# Filamint_Schematic_V4_1.net
KiCad netlist of a schematic drawn in EAGLE
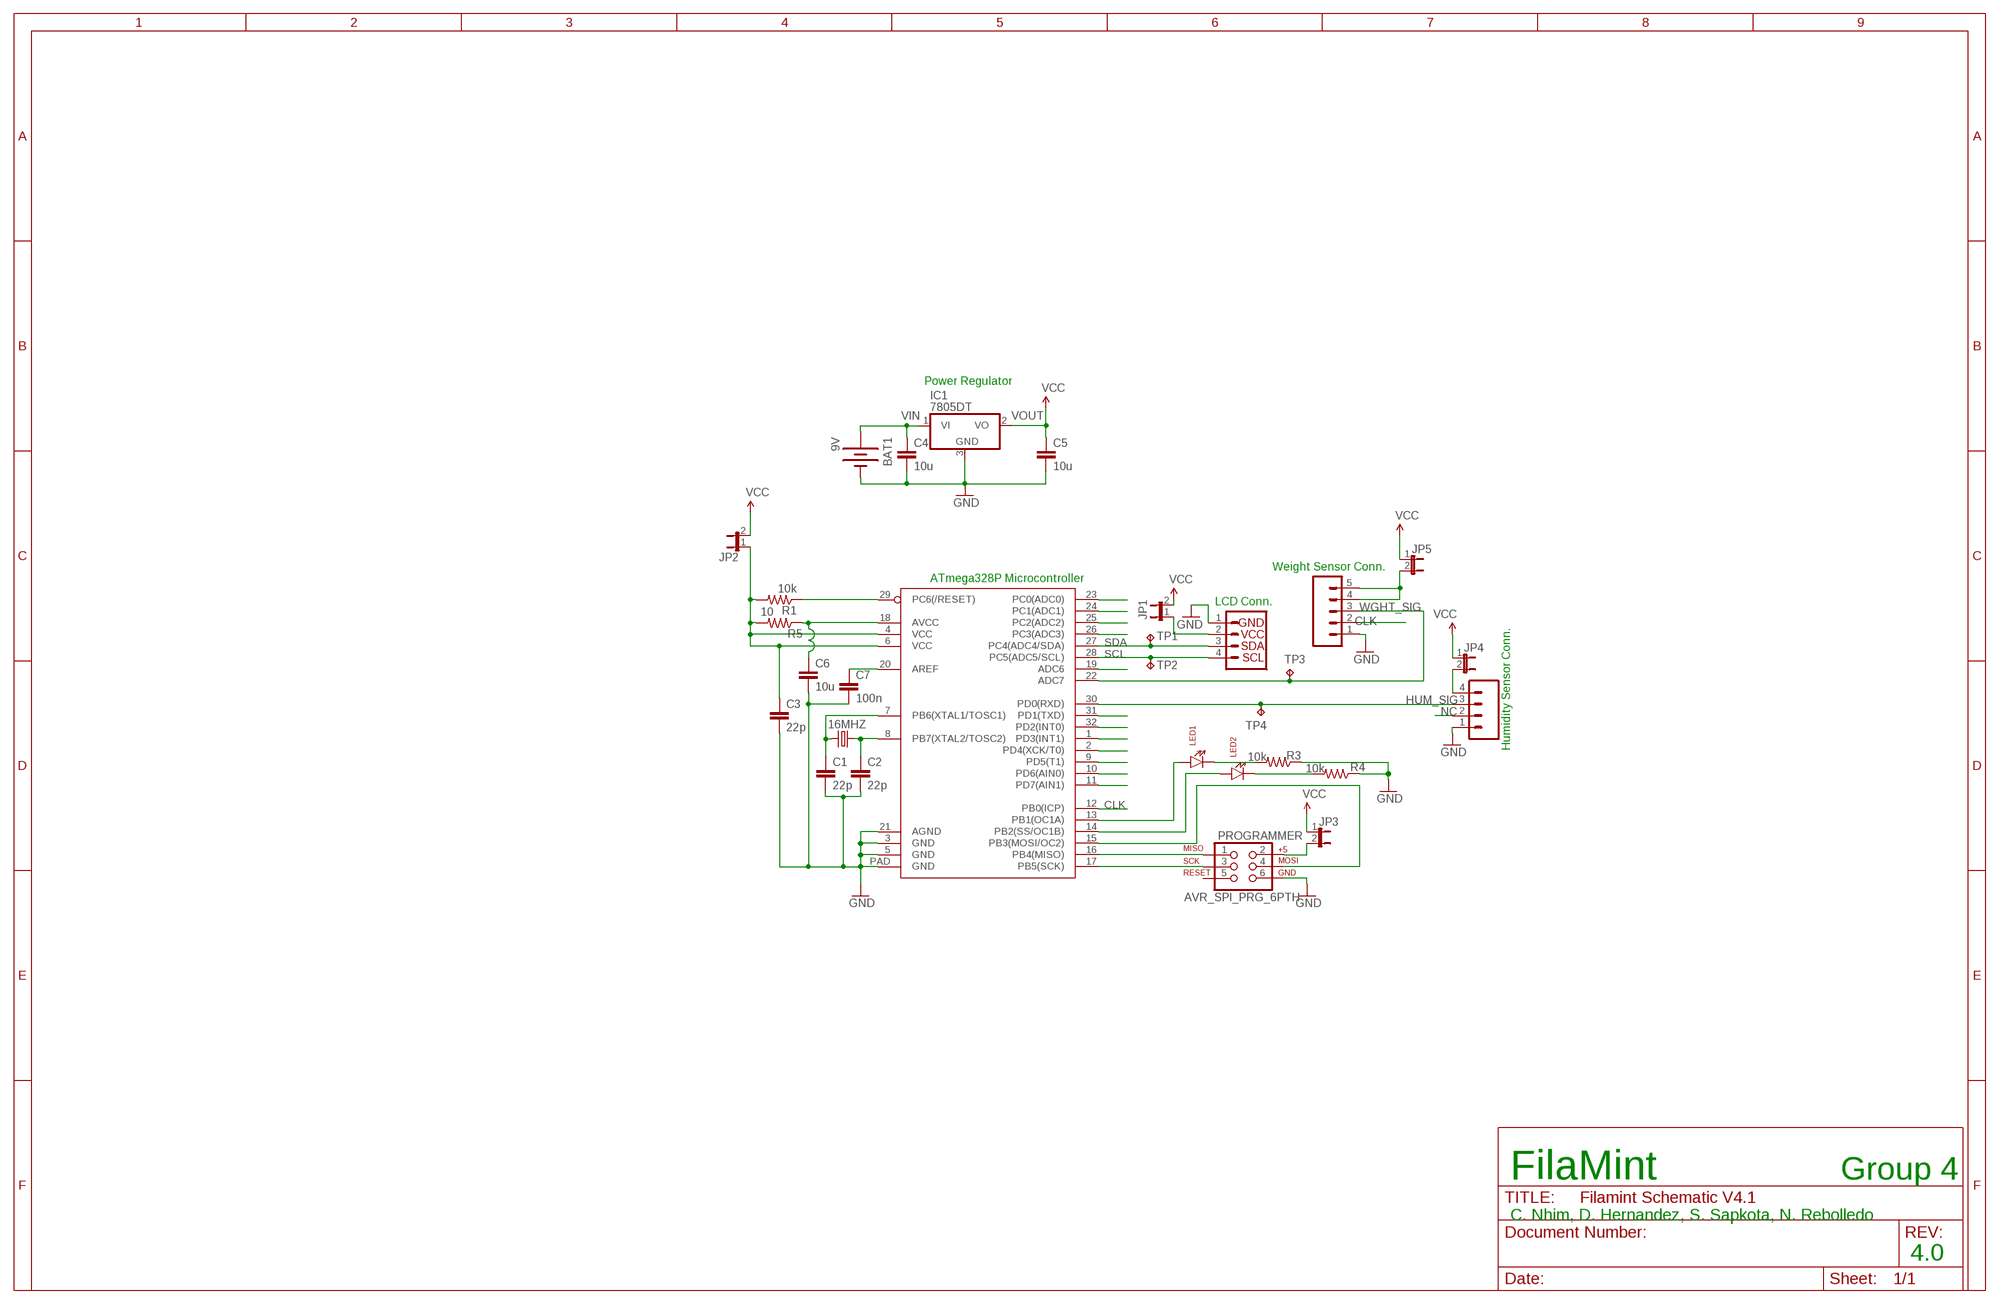
[diagram p0: schematic, sheet 1]

(export (version "E")
  (design (tool "Eeschema 10.0.6"))
  (components
    (comp (ref "16MHZ")
      (value "CSM-7X-DU")
      (footprint "eagle-import:CSM-7X-DU")
      (libsource (lib "eagle-import") (part "CSM-7X-DU"))
    )
    (comp (ref "BAT1")
      (value "9V")
      (footprint "eagle-import:BATTCON_9V")
      (libsource (lib "eagle-import") (part "BATTERY9V"))
    )
    (comp (ref "C1")
      (value "22p")
      (footprint "eagle-import:C025-024X044")
      (libsource (lib "eagle-import") (part "C-EU025-024X044"))
    )
    (comp (ref "C2")
      (value "22p")
      (footprint "eagle-import:C025-024X044")
      (libsource (lib "eagle-import") (part "C-EU025-024X044"))
    )
    (comp (ref "C3")
      (value "22p")
      (footprint "eagle-import:C025-024X044")
      (libsource (lib "eagle-import") (part "C-EU025-024X044"))
    )
    (comp (ref "C4")
      (value "10u")
      (footprint "eagle-import:C025-024X044")
      (libsource (lib "eagle-import") (part "C-EU025-024X044"))
    )
    (comp (ref "C5")
      (value "10u")
      (footprint "eagle-import:C025-024X044")
      (libsource (lib "eagle-import") (part "C-EU025-024X044"))
    )
    (comp (ref "C6")
      (value "10u")
      (footprint "eagle-import:C025-024X044")
      (libsource (lib "eagle-import") (part "C-EU025-024X044"))
    )
    (comp (ref "C7")
      (value "100n")
      (footprint "eagle-import:C025-024X044")
      (libsource (lib "eagle-import") (part "C-EU025-024X044"))
    )
    (comp (ref "DHT22")
      (value "M04SMD2")
      (footprint "eagle-import:1X04-1MM-RA")
      (libsource (lib "eagle-import") (part "M04SMD2"))
    )
    (comp (ref "HX711")
      (value "M05SMD")
      (footprint "eagle-import:1X05-1MM")
      (libsource (lib "eagle-import") (part "M05SMD"))
    )
    (comp (ref "IC1")
      (value "7805DT")
      (footprint "eagle-import:TO252")
      (libsource (lib "eagle-import") (part "78DT05"))
    )
    (comp (ref "JP1")
      (value "JP1E")
      (footprint "eagle-import:JP1")
      (libsource (lib "eagle-import") (part "JP1E"))
    )
    (comp (ref "JP2")
      (value "JP1E")
      (footprint "eagle-import:JP1")
      (libsource (lib "eagle-import") (part "JP1E"))
    )
    (comp (ref "JP3")
      (value "JP1E")
      (footprint "eagle-import:JP1")
      (libsource (lib "eagle-import") (part "JP1E"))
    )
    (comp (ref "JP4")
      (value "JP1E")
      (footprint "eagle-import:JP1")
      (libsource (lib "eagle-import") (part "JP1E"))
    )
    (comp (ref "JP5")
      (value "JP1E")
      (footprint "eagle-import:JP1")
      (libsource (lib "eagle-import") (part "JP1E"))
    )
    (comp (ref "LCD")
      (value "I2C_STANDARD")
      (footprint "eagle-import:1X04")
      (libsource (lib "eagle-import") (part "I2C_STANDARD"))
    )
    (comp (ref "LED1")
      (value "LTE-302")
      (footprint "eagle-import:LTE-302")
      (libsource (lib "eagle-import") (part "LTE-302"))
    )
    (comp (ref "LED2")
      (value "LTE-302")
      (footprint "eagle-import:LTE-302")
      (libsource (lib "eagle-import") (part "LTE-302"))
    )
    (comp (ref "MICROCONTROLLER")
      (value "ATMEGA328P_MLFMLF32")
      (footprint "eagle-import:MLF32-PAD")
      (libsource (lib "eagle-import") (part "ATMEGA328P_MLFMLF32"))
    )
    (comp (ref "PROGRAMMER")
      (value "AVR_SPI_PRG_6PTH")
      (footprint "eagle-import:2X3")
      (libsource (lib "eagle-import") (part "AVR_SPI_PRG_6PTH"))
    )
    (comp (ref "R1")
      (value "10k")
      (footprint "eagle-import:0204_5")
      (libsource (lib "eagle-import") (part "R-US_0204/5"))
    )
    (comp (ref "R3")
      (value "10k")
      (footprint "eagle-import:0204_5")
      (libsource (lib "eagle-import") (part "R-US_0204/5"))
    )
    (comp (ref "R4")
      (value "10k")
      (footprint "eagle-import:0204_5")
      (libsource (lib "eagle-import") (part "R-US_0204/5"))
    )
    (comp (ref "R5")
      (value "10")
      (footprint "eagle-import:0204_5")
      (libsource (lib "eagle-import") (part "R-US_0204/5"))
    )
    (comp (ref "TP1")
      (value "TPB1,27")
      (footprint "eagle-import:B1,27")
      (libsource (lib "eagle-import") (part "TPB1,27"))
    )
    (comp (ref "TP2")
      (value "TPB1,27")
      (footprint "eagle-import:B1,27")
      (libsource (lib "eagle-import") (part "TPB1,27"))
    )
    (comp (ref "TP3")
      (value "TPB1,27")
      (footprint "eagle-import:B1,27")
      (libsource (lib "eagle-import") (part "TPB1,27"))
    )
    (comp (ref "TP4")
      (value "TPB1,27")
      (footprint "eagle-import:B1,27")
      (libsource (lib "eagle-import") (part "TPB1,27"))
    )
  )
  (nets
    (net (code "1") (name "/CLK") (class "Default")
      (node (ref "HX711") (pin "2") (pinfunction "2_2") (pintype "passive"))
      (node (ref "MICROCONTROLLER") (pin "12") (pinfunction "PB0(ICP)_12") (pintype "bidirectional"))
    )
    (net (code "2") (name "/HUM_SIG") (class "Default")
      (node (ref "DHT22") (pin "3") (pinfunction "3_3") (pintype "passive"))
      (node (ref "MICROCONTROLLER") (pin "30") (pinfunction "PD0(RXD)_30") (pintype "bidirectional"))
      (node (ref "TP4") (pin "TP") (pinfunction "TP_TP") (pintype "input"))
    )
    (net (code "3") (name "/NC") (class "Default")
      (node (ref "DHT22") (pin "2") (pinfunction "2_2") (pintype "passive"))
    )
    (net (code "4") (name "/SCL") (class "Default")
      (node (ref "LCD") (pin "4") (pinfunction "4_4") (pintype "passive"))
      (node (ref "MICROCONTROLLER") (pin "28") (pinfunction "PC5(ADC5/SCL)_28") (pintype "bidirectional"))
      (node (ref "TP2") (pin "TP") (pinfunction "TP_TP") (pintype "input"))
    )
    (net (code "5") (name "/SDA") (class "Default")
      (node (ref "LCD") (pin "3") (pinfunction "3_3") (pintype "passive"))
      (node (ref "MICROCONTROLLER") (pin "27") (pinfunction "PC4(ADC4/SDA)_27") (pintype "bidirectional"))
      (node (ref "TP1") (pin "TP") (pinfunction "TP_TP") (pintype "input"))
    )
    (net (code "6") (name "/VIN") (class "Default")
      (node (ref "BAT1") (pin "+") (pinfunction "+_+") (pintype "power_in"))
      (node (ref "C4") (pin "1") (pinfunction "1_1") (pintype "passive"))
      (node (ref "IC1") (pin "1") (pinfunction "VI_1") (pintype "input"))
    )
    (net (code "7") (name "/WGHT_SIG") (class "Default")
      (node (ref "HX711") (pin "3") (pinfunction "3_3") (pintype "passive"))
      (node (ref "MICROCONTROLLER") (pin "22") (pinfunction "ADC7_22") (pintype "bidirectional"))
      (node (ref "TP3") (pin "TP") (pinfunction "TP_TP") (pintype "input"))
    )
    (net (code "8") (name "GND") (class "Default")
      (node (ref "BAT1") (pin "-") (pinfunction "-_-") (pintype "power_in"))
      (node (ref "C1") (pin "2") (pinfunction "2_2") (pintype "passive"))
      (node (ref "C2") (pin "2") (pinfunction "2_2") (pintype "passive"))
      (node (ref "C3") (pin "2") (pinfunction "2_2") (pintype "passive"))
      (node (ref "C4") (pin "2") (pinfunction "2_2") (pintype "passive"))
      (node (ref "C5") (pin "2") (pinfunction "2_2") (pintype "passive"))
      (node (ref "C6") (pin "2") (pinfunction "2_2") (pintype "passive"))
      (node (ref "C7") (pin "2") (pinfunction "2_2") (pintype "passive"))
      (node (ref "DHT22") (pin "1") (pinfunction "1_1") (pintype "passive"))
      (node (ref "HX711") (pin "1") (pinfunction "1_1") (pintype "passive"))
      (node (ref "IC1") (pin "3") (pinfunction "GND_3") (pintype "passive"))
      (node (ref "LCD") (pin "1") (pinfunction "1_1") (pintype "passive"))
      (node (ref "MICROCONTROLLER") (pin "21") (pinfunction "AGND_21") (pintype "bidirectional"))
      (node (ref "MICROCONTROLLER") (pin "3") (pinfunction "GND_3") (pintype "bidirectional"))
      (node (ref "MICROCONTROLLER") (pin "5") (pinfunction "GND_5") (pintype "bidirectional"))
      (node (ref "MICROCONTROLLER") (pin "PAD") (pinfunction "GND_PAD") (pintype "bidirectional"))
      (node (ref "PROGRAMMER") (pin "6") (pinfunction "6_6") (pintype "passive"))
      (node (ref "R3") (pin "1") (pinfunction "1_1") (pintype "passive"))
      (node (ref "R4") (pin "1") (pinfunction "1_1") (pintype "passive"))
    )
    (net (code "9") (name "Net-(C3-Pad1)") (class "Default")
      (node (ref "C3") (pin "1") (pinfunction "1_1") (pintype "passive"))
      (node (ref "JP2") (pin "1") (pinfunction "1_1") (pintype "passive"))
      (node (ref "MICROCONTROLLER") (pin "4") (pinfunction "VCC_4") (pintype "bidirectional"))
      (node (ref "MICROCONTROLLER") (pin "6") (pinfunction "VCC_6") (pintype "bidirectional"))
      (node (ref "R1") (pin "2") (pinfunction "2_2") (pintype "passive"))
      (node (ref "R5") (pin "2") (pinfunction "2_2") (pintype "passive"))
    )
    (net (code "10") (name "Net-(DHT22-Pad4)") (class "Default")
      (node (ref "DHT22") (pin "4") (pinfunction "4_4") (pintype "passive"))
      (node (ref "JP4") (pin "2") (pinfunction "2_2") (pintype "passive"))
    )
    (net (code "11") (name "Net-(HX711-Pad4)") (class "Default")
      (node (ref "HX711") (pin "4") (pinfunction "4_4") (pintype "passive"))
      (node (ref "HX711") (pin "5") (pinfunction "5_5") (pintype "passive"))
      (node (ref "JP5") (pin "2") (pinfunction "2_2") (pintype "passive"))
    )
    (net (code "12") (name "Net-(JP1-Pad1)") (class "Default")
      (node (ref "JP1") (pin "1") (pinfunction "1_1") (pintype "passive"))
      (node (ref "LCD") (pin "2") (pinfunction "2_2") (pintype "passive"))
    )
    (net (code "13") (name "Net-(JP3-Pad2)") (class "Default")
      (node (ref "JP3") (pin "2") (pinfunction "2_2") (pintype "passive"))
      (node (ref "PROGRAMMER") (pin "2") (pinfunction "2_2") (pintype "passive"))
    )
    (net (code "14") (name "Net-(LED1-PadC)") (class "Default")
      (node (ref "LED1") (pin "C") (pinfunction "C_C") (pintype "bidirectional"))
      (node (ref "R3") (pin "2") (pinfunction "2_2") (pintype "passive"))
    )
    (net (code "15") (name "Net-(LED2-PadC)") (class "Default")
      (node (ref "LED2") (pin "C") (pinfunction "C_C") (pintype "bidirectional"))
      (node (ref "R4") (pin "2") (pinfunction "2_2") (pintype "passive"))
    )
    (net (code "16") (name "Net-(MICROCONTROLLER-AREF)") (class "Default")
      (node (ref "C7") (pin "1") (pinfunction "1_1") (pintype "passive"))
      (node (ref "MICROCONTROLLER") (pin "20") (pinfunction "AREF_20") (pintype "bidirectional"))
    )
    (net (code "17") (name "Net-(MICROCONTROLLER-AVCC)") (class "Default")
      (node (ref "C6") (pin "1") (pinfunction "1_1") (pintype "passive"))
      (node (ref "MICROCONTROLLER") (pin "18") (pinfunction "AVCC_18") (pintype "bidirectional"))
      (node (ref "R5") (pin "1") (pinfunction "1_1") (pintype "passive"))
    )
    (net (code "18") (name "Net-(MICROCONTROLLER-PB1(OC1A))") (class "Default")
      (node (ref "LED1") (pin "A") (pinfunction "A_A") (pintype "bidirectional"))
      (node (ref "MICROCONTROLLER") (pin "13") (pinfunction "PB1(OC1A)_13") (pintype "bidirectional"))
    )
    (net (code "19") (name "Net-(MICROCONTROLLER-PB2(SS{slash}OC1B))") (class "Default")
      (node (ref "LED2") (pin "A") (pinfunction "A_A") (pintype "bidirectional"))
      (node (ref "MICROCONTROLLER") (pin "14") (pinfunction "PB2(SS/OC1B)_14") (pintype "bidirectional"))
    )
    (net (code "20") (name "Net-(MICROCONTROLLER-PB3(MOSI{slash}OC2))") (class "Default")
      (node (ref "MICROCONTROLLER") (pin "15") (pinfunction "PB3(MOSI/OC2)_15") (pintype "bidirectional"))
      (node (ref "PROGRAMMER") (pin "4") (pinfunction "4_4") (pintype "passive"))
    )
    (net (code "21") (name "Net-(MICROCONTROLLER-PB4(MISO))") (class "Default")
      (node (ref "MICROCONTROLLER") (pin "16") (pinfunction "PB4(MISO)_16") (pintype "bidirectional"))
      (node (ref "PROGRAMMER") (pin "1") (pinfunction "1_1") (pintype "passive"))
    )
    (net (code "22") (name "Net-(MICROCONTROLLER-PB5(SCK))") (class "Default")
      (node (ref "MICROCONTROLLER") (pin "17") (pinfunction "PB5(SCK)_17") (pintype "bidirectional"))
      (node (ref "PROGRAMMER") (pin "3") (pinfunction "3_3") (pintype "passive"))
    )
    (net (code "23") (name "Net-(MICROCONTROLLER-PB6(XTAL1{slash}TOSC1))") (class "Default")
      (node (ref "16MHZ") (pin "2") (pinfunction "2_2") (pintype "passive"))
      (node (ref "C1") (pin "1") (pinfunction "1_1") (pintype "passive"))
      (node (ref "MICROCONTROLLER") (pin "7") (pinfunction "PB6(XTAL1/TOSC1)_7") (pintype "bidirectional"))
    )
    (net (code "24") (name "Net-(MICROCONTROLLER-PB7(XTAL2{slash}TOSC2))") (class "Default")
      (node (ref "16MHZ") (pin "1") (pinfunction "1_1") (pintype "passive"))
      (node (ref "C2") (pin "1") (pinfunction "1_1") (pintype "passive"))
      (node (ref "MICROCONTROLLER") (pin "8") (pinfunction "PB7(XTAL2/TOSC2)_8") (pintype "bidirectional"))
    )
    (net (code "25") (name "Net-(MICROCONTROLLER-PC6({slash}RESET))") (class "Default")
      (node (ref "MICROCONTROLLER") (pin "29") (pinfunction "PC6(/RESET)_29") (pintype "bidirectional"))
      (node (ref "R1") (pin "1") (pinfunction "1_1") (pintype "passive"))
    )
    (net (code "26") (name "VCC") (class "Default")
      (node (ref "C5") (pin "1") (pinfunction "1_1") (pintype "passive"))
      (node (ref "IC1") (pin "2") (pinfunction "VO_2") (pintype "passive"))
      (node (ref "JP1") (pin "2") (pinfunction "2_2") (pintype "passive"))
      (node (ref "JP2") (pin "2") (pinfunction "2_2") (pintype "passive"))
      (node (ref "JP3") (pin "1") (pinfunction "1_1") (pintype "passive"))
      (node (ref "JP4") (pin "1") (pinfunction "1_1") (pintype "passive"))
      (node (ref "JP5") (pin "1") (pinfunction "1_1") (pintype "passive"))
    )
    (net (code "27") (name "unconnected-(MICROCONTROLLER-ADC6-Pad19)") (class "Default")
      (node (ref "MICROCONTROLLER") (pin "19") (pinfunction "ADC6_19") (pintype "bidirectional"))
    )
    (net (code "28") (name "unconnected-(MICROCONTROLLER-PC0(ADC0)-Pad23)") (class "Default")
      (node (ref "MICROCONTROLLER") (pin "23") (pinfunction "PC0(ADC0)_23") (pintype "bidirectional"))
    )
    (net (code "29") (name "unconnected-(MICROCONTROLLER-PC1(ADC1)-Pad24)") (class "Default")
      (node (ref "MICROCONTROLLER") (pin "24") (pinfunction "PC1(ADC1)_24") (pintype "bidirectional"))
    )
    (net (code "30") (name "unconnected-(MICROCONTROLLER-PC2(ADC2)-Pad25)") (class "Default")
      (node (ref "MICROCONTROLLER") (pin "25") (pinfunction "PC2(ADC2)_25") (pintype "bidirectional"))
    )
    (net (code "31") (name "unconnected-(MICROCONTROLLER-PC3(ADC3)-Pad26)") (class "Default")
      (node (ref "MICROCONTROLLER") (pin "26") (pinfunction "PC3(ADC3)_26") (pintype "bidirectional"))
    )
    (net (code "32") (name "unconnected-(MICROCONTROLLER-PD1(TXD)-Pad31)") (class "Default")
      (node (ref "MICROCONTROLLER") (pin "31") (pinfunction "PD1(TXD)_31") (pintype "bidirectional"))
    )
    (net (code "33") (name "unconnected-(MICROCONTROLLER-PD2(INT0)-Pad32)") (class "Default")
      (node (ref "MICROCONTROLLER") (pin "32") (pinfunction "PD2(INT0)_32") (pintype "bidirectional"))
    )
    (net (code "34") (name "unconnected-(MICROCONTROLLER-PD3(INT1)-Pad1)") (class "Default")
      (node (ref "MICROCONTROLLER") (pin "1") (pinfunction "PD3(INT1)_1") (pintype "bidirectional"))
    )
    (net (code "35") (name "unconnected-(MICROCONTROLLER-PD4(XCK{slash}T0)-Pad2)") (class "Default")
      (node (ref "MICROCONTROLLER") (pin "2") (pinfunction "PD4(XCK/T0)_2") (pintype "bidirectional"))
    )
    (net (code "36") (name "unconnected-(MICROCONTROLLER-PD5(T1)-Pad9)") (class "Default")
      (node (ref "MICROCONTROLLER") (pin "9") (pinfunction "PD5(T1)_9") (pintype "bidirectional"))
    )
    (net (code "37") (name "unconnected-(MICROCONTROLLER-PD6(AIN0)-Pad10)") (class "Default")
      (node (ref "MICROCONTROLLER") (pin "10") (pinfunction "PD6(AIN0)_10") (pintype "bidirectional"))
    )
    (net (code "38") (name "unconnected-(MICROCONTROLLER-PD7(AIN1)-Pad11)") (class "Default")
      (node (ref "MICROCONTROLLER") (pin "11") (pinfunction "PD7(AIN1)_11") (pintype "bidirectional"))
    )
    (net (code "39") (name "unconnected-(PROGRAMMER-Pad5)") (class "Default")
      (node (ref "PROGRAMMER") (pin "5") (pinfunction "5_5") (pintype "passive"))
    )
  )
)
